# MSP430.net
KiCad netlist of a schematic drawn in Altium Designer
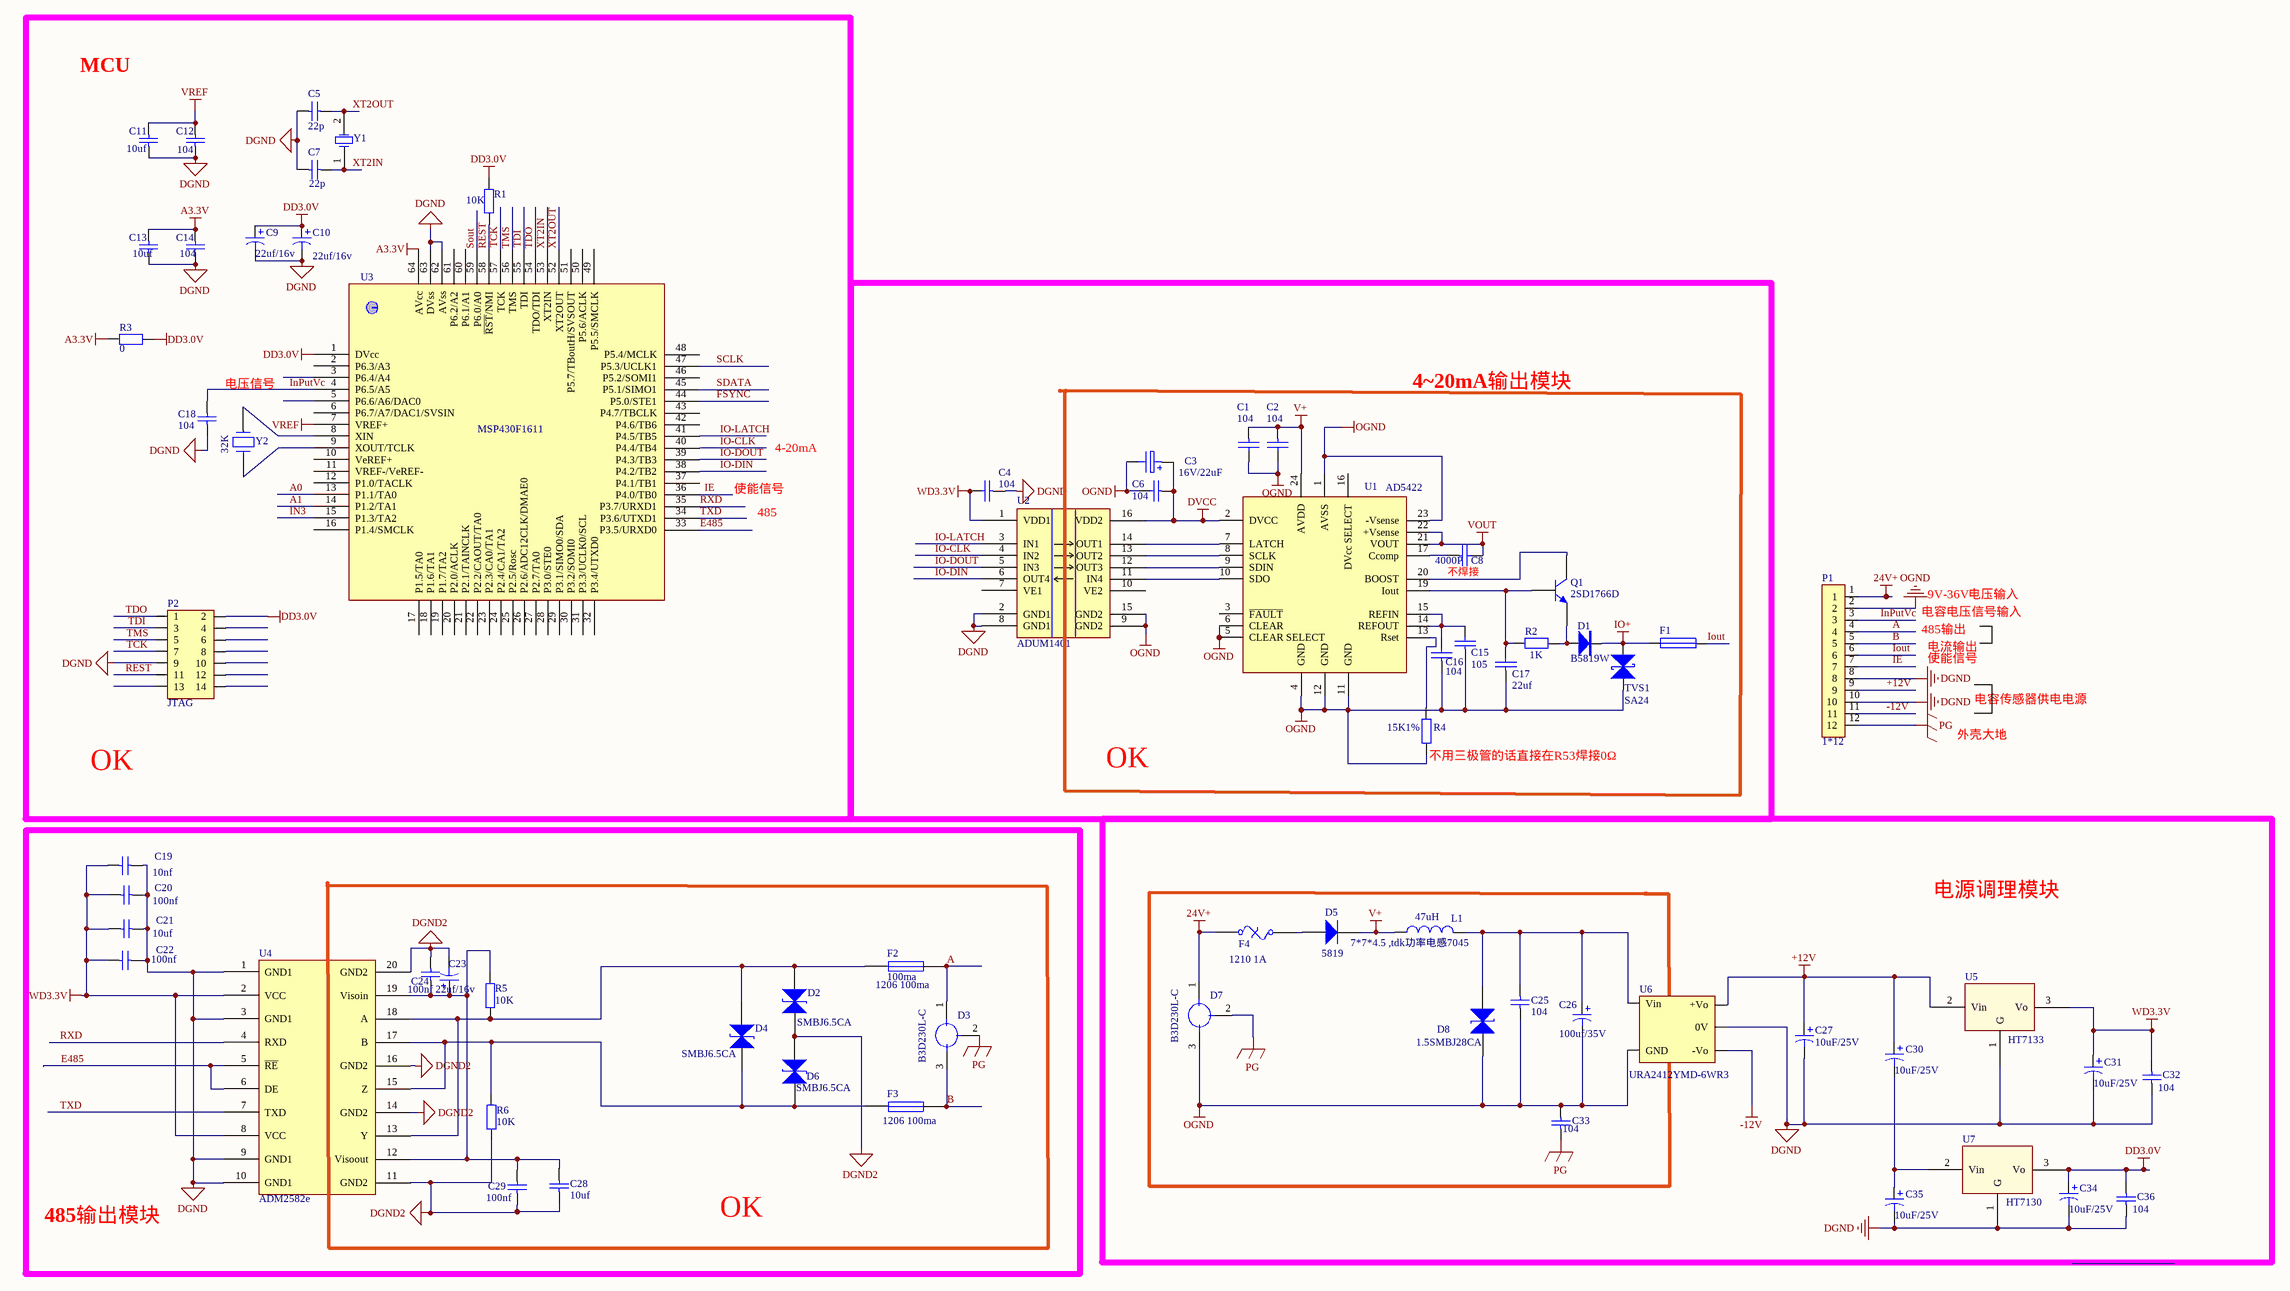
[diagram p0: MSP430.SchDoc]

(export (version "E")
  (design (tool "Eeschema 10.0.6"))
  (components
    (comp (ref "C1") (value "104") (footprint "0805") (libsource (lib "*") (part "CAP")))
    (comp (ref "C2") (value "104") (footprint "0805") (libsource (lib "*") (part "CAP")))
    (comp (ref "C3") (value "16V/22uF") (footprint "3216") (libsource (lib "*") (part "ELECTRO1")))
    (comp (ref "C4") (value "104") (footprint "0805") (libsource (lib "*") (part "CAP")))
    (comp (ref "C5")
      (value "22p")
      (footprint "0805")
      (description "Capacitor")
      (fields (field (name "PUBLISHER") "Altium Limited"))
      (libsource (lib "") (part "Cap_1"))
    )
    (comp (ref "C6") (value "104") (footprint "0805") (libsource (lib "*") (part "CAP")))
    (comp (ref "C7")
      (value "22p")
      (footprint "0805")
      (description "Capacitor")
      (fields (field (name "PUBLISHER") "Altium Limited"))
      (libsource (lib "") (part "Cap_1"))
    )
    (comp (ref "C8") (value "4000P") (footprint "0805") (libsource (lib "*") (part "CAP")))
    (comp (ref "C9")
      (value "22uf/16v")
      (footprint "B型 3528")
      (fields (field (name "ALTIUM_UNNAMED_1") "22uf/16v"))
      (libsource (lib "元器件") (part "Cap Pol2_B"))
    )
    (comp (ref "C10")
      (value "22uf/16v")
      (footprint "B型 3528")
      (fields (field (name "ALTIUM_UNNAMED_1") "22uf/16v"))
      (libsource (lib "元器件") (part "Cap Pol2_B"))
    )
    (comp (ref "C11")
      (value "10uf")
      (footprint "0805")
      (description "Capacitor")
      (fields (field (name "PUBLISHER") "Altium Limited"))
      (libsource (lib "Miscellaneous Devices") (part "Cap"))
    )
    (comp (ref "C12")
      (value "104")
      (footprint "0805")
      (description "Capacitor")
      (fields (field (name "PUBLISHER") "Altium Limited"))
      (libsource (lib "Miscellaneous Devices") (part "Cap"))
    )
    (comp (ref "C13")
      (value "10uf")
      (footprint "0805")
      (description "Capacitor")
      (fields (field (name "PUBLISHER") "Altium Limited"))
      (libsource (lib "Miscellaneous Devices") (part "Cap"))
    )
    (comp (ref "C14")
      (value "104")
      (footprint "0805")
      (description "Capacitor")
      (fields (field (name "PUBLISHER") "Altium Limited"))
      (libsource (lib "Miscellaneous Devices") (part "Cap"))
    )
    (comp (ref "C15") (value "105") (footprint "0805") (libsource (lib "*") (part "CAP")))
    (comp (ref "C16") (value "104") (footprint "0805") (libsource (lib "*") (part "CAP")))
    (comp (ref "C17") (value "22uf") (footprint "0805") (libsource (lib "*") (part "CAP")))
    (comp (ref "C18")
      (value "104")
      (footprint "0805")
      (description "Capacitor")
      (fields (field (name "PUBLISHER") "Altium Limited"))
      (libsource (lib "元器件") (part "Cap_1"))
    )
    (comp (ref "C19")
      (value "10nf")
      (footprint "0805")
      (description "Capacitor")
      (fields (field (name "PUBLISHER") "Altium Limited"))
      (libsource (lib "元器件") (part "Cap_1"))
    )
    (comp (ref "C20")
      (value "100nf")
      (footprint "0805")
      (description "Capacitor")
      (fields (field (name "PUBLISHER") "Altium Limited"))
      (libsource (lib "元器件") (part "Cap_1"))
    )
    (comp (ref "C21")
      (value "10uf")
      (footprint "0805")
      (description "Capacitor")
      (fields (field (name "PUBLISHER") "Altium Limited"))
      (libsource (lib "元器件") (part "Cap_1"))
    )
    (comp (ref "C22")
      (value "100nf")
      (footprint "0805")
      (description "Capacitor")
      (fields (field (name "PUBLISHER") "Altium Limited"))
      (libsource (lib "元器件") (part "Cap_1"))
    )
    (comp (ref "C23")
      (value "22uf/16v")
      (footprint "B型 3528")
      (fields (field (name "ALTIUM_UNNAMED_1") "22uf/16v"))
      (libsource (lib "元器件") (part "Cap Pol2_B"))
    )
    (comp (ref "C24")
      (value "100nf")
      (footprint "0805")
      (description "Capacitor")
      (fields (field (name "PUBLISHER") "Altium Limited"))
      (libsource (lib "元器件") (part "Cap_1"))
    )
    (comp (ref "C25")
      (value "104")
      (footprint "0805")
      (description "Capacitor")
      (fields (field (name "PUBLISHER") "Altium Limited"))
      (libsource (lib "元器件") (part "Cap_1"))
    )
    (comp (ref "C26")
      (value "100uf/35V")
      (footprint "C5X5")
      (description "Polarized Capacitor (Axial)")
      (fields (field (name "Comment") "10uf/35V") (field (name "PUBLISHER") "Altium Limited"))
      (libsource (lib "元器件") (part "Cap Pol2"))
    )
    (comp (ref "C27")
      (value "10uF/25V")
      (footprint "3216")
      (description "Polarized Capacitor (Radial)")
      (fields (field (name "PUBLISHER") "Altium Limited"))
      (libsource (lib "Miscellaneous Devices") (part "Cap Pol1"))
    )
    (comp (ref "C28")
      (value "10uf")
      (footprint "0805")
      (description "Capacitor")
      (fields (field (name "PUBLISHER") "Altium Limited"))
      (libsource (lib "元器件") (part "Cap_1"))
    )
    (comp (ref "C29")
      (value "100nf")
      (footprint "0805")
      (description "Capacitor")
      (fields (field (name "PUBLISHER") "Altium Limited"))
      (libsource (lib "元器件") (part "Cap_1"))
    )
    (comp (ref "C30")
      (value "10uF/25V")
      (footprint "3216")
      (description "Polarized Capacitor (Radial)")
      (fields (field (name "Comment") "10uF") (field (name "PUBLISHER") "Altium Limited"))
      (libsource (lib "Miscellaneous Devices") (part "Cap Pol1"))
    )
    (comp (ref "C31")
      (value "10uF/25V")
      (footprint "3216")
      (description "Polarized Capacitor (Radial)")
      (fields (field (name "Comment") "10uF") (field (name "PUBLISHER") "Altium Limited"))
      (libsource (lib "Miscellaneous Devices") (part "Cap Pol1"))
    )
    (comp (ref "C32")
      (value "104")
      (footprint "0805")
      (description "Capacitor")
      (fields (field (name "PUBLISHER") "Altium Limited"))
      (libsource (lib "") (part "Cap_1"))
    )
    (comp (ref "C33")
      (value "104")
      (footprint "1812")
      (description "Capacitor")
      (fields (field (name "PUBLISHER") "Altium Limited"))
      (libsource (lib "元器件") (part "Cap_1"))
    )
    (comp (ref "C34")
      (value "10uF/25V")
      (footprint "3216")
      (description "Polarized Capacitor (Radial)")
      (fields (field (name "Comment") "10uF") (field (name "PUBLISHER") "Altium Limited"))
      (libsource (lib "Miscellaneous Devices") (part "Cap Pol1"))
    )
    (comp (ref "C35")
      (value "10uF/25V")
      (footprint "3216")
      (description "Polarized Capacitor (Radial)")
      (fields (field (name "Comment") "10uF") (field (name "PUBLISHER") "Altium Limited"))
      (libsource (lib "Miscellaneous Devices") (part "Cap Pol1"))
    )
    (comp (ref "C36")
      (value "104")
      (footprint "0805")
      (description "Capacitor")
      (fields (field (name "PUBLISHER") "Altium Limited"))
      (libsource (lib "") (part "Cap_1"))
    )
    (comp (ref "D1")
      (value "B5819W")
      (footprint "7227-D")
      (description "Diode")
      (libsource (lib "*") (part "B5819W"))
    )
    (comp (ref "D2") (value "SMBJ6.5CA") (footprint "7227-D") (libsource (lib "Tm") (part "TVS")))
    (comp (ref "D3")
      (value "B3D230L-C")
      (footprint "B3D090L-C")
      (libsource (lib "Schlib1") (part "B3D230L-C"))
    )
    (comp (ref "D4") (value "SMBJ6.5CA") (footprint "7227-D") (libsource (lib "Tm") (part "TVS")))
    (comp (ref "D5")
      (value "5819")
      (footprint "7227-D")
      (description "Default Diode")
      (fields (field (name "PUBLISHER") "Altium Limited"))
      (libsource (lib "I5pcb库") (part "Diode"))
    )
    (comp (ref "D6") (value "SMBJ6.5CA") (footprint "7227-D") (libsource (lib "Tm") (part "TVS")))
    (comp (ref "D7")
      (value "B3D230L-C")
      (footprint "B3D090L-C")
      (libsource (lib "Schlib1") (part "B3D230L-C"))
    )
    (comp (ref "D8") (value "1.5SMBJ28CA") (footprint "7227-D") (libsource (lib "Tm") (part "TVS")))
    (comp (ref "F1") (value "~") (footprint "1206") (description "Fuse") (libsource (lib "*") (part "FUSE1")))
    (comp (ref "F2")
      (value "100ma")
      (footprint "1206R")
      (description "Fuse")
      (fields (field (name "PUBLISHER") "Altium Limited"))
      (libsource (lib "Miscellaneous Devices") (part "Fuse 1"))
    )
    (comp (ref "F3")
      (value "100ma")
      (footprint "1206R")
      (description "Fuse")
      (fields (field (name "PUBLISHER") "Altium Limited"))
      (libsource (lib "Miscellaneous Devices") (part "Fuse 1"))
    )
    (comp (ref "F4")
      (value "Fuse Thermal  200ma")
      (footprint "1210")
      (description "Thermal Fuse")
      (fields (field (name "PUBLISHER") "Altium Limited"))
      (libsource (lib "Miscellaneous Devices") (part "Fuse Thermal"))
    )
    (comp (ref "L1")
      (value "47uH")
      (footprint "L7X7")
      (description "Inductor")
      (fields (field (name "Comment") "100uH") (field (name "PUBLISHER") "Altium Limited"))
      (libsource (lib "Miscellaneous Devices") (part "Inductor"))
    )
    (comp (ref "P1") (value "1*12") (libsource (lib "元器件") (part "1*12")))
    (comp (ref "P2") (value "JTAG") (footprint "14缺口") (libsource (lib "元器件") (part "2*7")))
    (comp (ref "Q1")
      (value "2SD1766D")
      (footprint "SOT-89-2")
      (description "NPN General Purpose Amplifier")
      (fields (field (name "PUBLISHER") "Altium Limited"))
      (libsource (lib "元器件") (part "NPN"))
    )
    (comp (ref "R1")
      (value "10K")
      (footprint "0805")
      (description "Resistor")
      (fields (field (name "PUBLISHER") "Altium Limited"))
      (libsource (lib "") (part "Res2_1"))
    )
    (comp (ref "R2")
      (value "1K")
      (footprint "0805")
      (description "Resistor")
      (fields (field (name "PUBLISHER") "Altium Limited"))
      (libsource (lib "") (part "Res2_3"))
    )
    (comp (ref "R3")
      (value "0")
      (footprint "0805")
      (description "Resistor")
      (fields (field (name "PUBLISHER") "Altium Limited"))
      (libsource (lib "Miscellaneous Devices") (part "Res2"))
    )
    (comp (ref "R4")
      (value "15K1%")
      (footprint "0805")
      (description "Resistor")
      (fields (field (name "PUBLISHER") "Altium Limited"))
      (libsource (lib "PRJ_FZ") (part "Res2"))
    )
    (comp (ref "R5")
      (value "10K")
      (footprint "0805")
      (description "Resistor")
      (fields (field (name "PUBLISHER") "Altium Limited"))
      (libsource (lib "") (part "Res2_2"))
    )
    (comp (ref "R6")
      (value "10K")
      (footprint "0805")
      (description "Resistor")
      (fields (field (name "PUBLISHER") "Altium Limited"))
      (libsource (lib "") (part "Res2_2"))
    )
    (comp (ref "TVS1") (value "SA24") (footprint "7227-D") (libsource (lib "*") (part "TVS")))
    (comp (ref "U1") (value "AD5422") (footprint "AD5422") (libsource (lib "元器件") (part "AD5422")))
    (comp (ref "U2") (value "ADUM1401") (footprint "SO16W") (libsource (lib "元器件") (part "ADUM1401")))
    (comp (ref "U3")
      (value "MSP430F1611")
      (footprint "PM")
      (description "MSP430F1611IPM")
      (libsource (lib "*") (part "MSP430F1611IPM"))
    )
    (comp (ref "U4") (value "ADM2582e") (footprint "AM258XXX") (libsource (lib "元器件") (part "ADM258XXX")))
    (comp (ref "U5") (value "HT7133") (footprint "SOT-89-2") (libsource (lib "元器件") (part "HT7150-1")))
    (comp (ref "U6") (value "URA2412YMD-6WR3") (libsource (lib "元器件") (part "URB2409YMD-6WR3_1 双路")))
    (comp (ref "U7") (value "HT7130") (footprint "SOT-89-2") (libsource (lib "元器件") (part "HT7150-1")))
    (comp (ref "Y1")
      (value "8M")
      (footprint "5032")
      (description "Crystal Oscillator")
      (fields (field (name "PUBLISHER") "Altium Limited"))
      (libsource (lib "Miscellaneous Devices") (part "XTAL"))
    )
    (comp (ref "Y2")
      (value "32K")
      (footprint "FC-135")
      (description "Crystal")
      (libsource (lib "*") (part "CRYSTAL"))
    )
  )
  (nets
    (net (code "1") (name "+12V") (class "Default")
      (node (ref "C27") (pin "1") (pinfunction "1_1") (pintype "passive"))
      (node (ref "C30") (pin "1") (pinfunction "1_1") (pintype "passive"))
      (node (ref "P1") (pin "9") (pinfunction "9_9") (pintype "passive"))
      (node (ref "U5") (pin "2") (pinfunction "Vin_2") (pintype "passive"))
    )
    (net (code "2") (name "-12V") (class "Default")
      (node (ref "P1") (pin "11") (pinfunction "11_11") (pintype "passive"))
      (node (ref "U6") (pin "4") (pinfunction "-Vo_4") (pintype "passive"))
    )
    (net (code "3") (name "/A") (class "Default")
      (node (ref "D3") (pin "1") (pinfunction "1_1") (pintype "passive"))
      (node (ref "F2") (pin "2") (pinfunction "2_2") (pintype "passive"))
      (node (ref "P1") (pin "4") (pinfunction "4_4") (pintype "passive"))
    )
    (net (code "4") (name "/A0") (class "Default")
      (node (ref "U3") (pin "13") (pinfunction "P1.1/TA0_13") (pintype "passive"))
    )
    (net (code "5") (name "/A1") (class "Default")
      (node (ref "U3") (pin "14") (pinfunction "P1.2/TA1_14") (pintype "passive"))
    )
    (net (code "6") (name "/B") (class "Default")
      (node (ref "D3") (pin "3") (pinfunction "3_3") (pintype "passive"))
      (node (ref "F3") (pin "2") (pinfunction "2_2") (pintype "passive"))
      (node (ref "P1") (pin "5") (pinfunction "5_5") (pintype "passive"))
    )
    (net (code "7") (name "/E485") (class "Default")
      (node (ref "U3") (pin "33") (pinfunction "P3.5/URXD0_33") (pintype "passive"))
      (node (ref "U4") (pin "5") (pinfunction "~{RE}_5") (pintype "passive"))
      (node (ref "U4") (pin "6") (pinfunction "DE_6") (pintype "passive"))
    )
    (net (code "8") (name "/FSYNC") (class "Default")
      (node (ref "U3") (pin "44") (pinfunction "P5.0/STE1_44") (pintype "passive"))
    )
    (net (code "9") (name "/IE") (class "Default")
      (node (ref "P1") (pin "7") (pinfunction "7_7") (pintype "passive"))
      (node (ref "U3") (pin "36") (pinfunction "P4.0/TB0_36") (pintype "passive"))
    )
    (net (code "10") (name "/IN3") (class "Default")
      (node (ref "U3") (pin "15") (pinfunction "P1.3/TA2_15") (pintype "passive"))
    )
    (net (code "11") (name "/IO-CLK") (class "Default")
      (node (ref "U2") (pin "4") (pinfunction "IN2_4") (pintype "passive"))
      (node (ref "U3") (pin "40") (pinfunction "P4.4/TB4_40") (pintype "passive"))
    )
    (net (code "12") (name "/IO-DIN") (class "Default")
      (node (ref "U2") (pin "6") (pinfunction "OUT4_6") (pintype "passive"))
      (node (ref "U3") (pin "38") (pinfunction "P4.2/TB2_38") (pintype "passive"))
    )
    (net (code "13") (name "/IO-DOUT") (class "Default")
      (node (ref "U2") (pin "5") (pinfunction "IN3_5") (pintype "passive"))
      (node (ref "U3") (pin "39") (pinfunction "P4.3/TB3_39") (pintype "passive"))
    )
    (net (code "14") (name "/IO-LATCH") (class "Default")
      (node (ref "U2") (pin "3") (pinfunction "IN1_3") (pintype "passive"))
      (node (ref "U3") (pin "41") (pinfunction "P4.5/TB5_41") (pintype "passive"))
    )
    (net (code "15") (name "/InPutVc") (class "Default")
      (node (ref "C18") (pin "2") (pinfunction "2_2") (pintype "passive"))
      (node (ref "P1") (pin "3") (pinfunction "3_3") (pintype "passive"))
      (node (ref "U3") (pin "4") (pinfunction "P6.5/A5_4") (pintype "passive"))
    )
    (net (code "16") (name "/Iout") (class "Default")
      (node (ref "F1") (pin "1") (pinfunction "1_1") (pintype "passive"))
      (node (ref "P1") (pin "6") (pinfunction "6_6") (pintype "passive"))
    )
    (net (code "17") (name "/REST") (class "Default")
      (node (ref "P2") (pin "11") (pinfunction "11_11") (pintype "passive"))
      (node (ref "R1") (pin "1") (pinfunction "1_1") (pintype "passive"))
      (node (ref "U3") (pin "58") (pinfunction "~{RST}/NMI_58") (pintype "passive"))
    )
    (net (code "18") (name "/RXD") (class "Default")
      (node (ref "U3") (pin "35") (pinfunction "P3.7/URXD1_35") (pintype "passive"))
      (node (ref "U4") (pin "4") (pinfunction "RXD_4") (pintype "passive"))
    )
    (net (code "19") (name "/SCLK") (class "Default")
      (node (ref "U3") (pin "47") (pinfunction "P5.3/UCLK1_47") (pintype "passive"))
    )
    (net (code "20") (name "/SDATA") (class "Default")
      (node (ref "U3") (pin "45") (pinfunction "P5.1/SIMO1_45") (pintype "passive"))
    )
    (net (code "21") (name "/Sout") (class "Default")
      (node (ref "U3") (pin "59") (pinfunction "P6.0/A0_59") (pintype "passive"))
    )
    (net (code "22") (name "/TCK") (class "Default")
      (node (ref "P2") (pin "7") (pinfunction "7_7") (pintype "passive"))
      (node (ref "U3") (pin "57") (pinfunction "TCK_57") (pintype "passive"))
    )
    (net (code "23") (name "/TDI") (class "Default")
      (node (ref "P2") (pin "3") (pinfunction "3_3") (pintype "passive"))
      (node (ref "U3") (pin "55") (pinfunction "TDI_55") (pintype "passive"))
    )
    (net (code "24") (name "/TDO") (class "Default")
      (node (ref "P2") (pin "1") (pinfunction "1_1") (pintype "passive"))
      (node (ref "U3") (pin "54") (pinfunction "TDO/TDI_54") (pintype "passive"))
    )
    (net (code "25") (name "/TMS") (class "Default")
      (node (ref "P2") (pin "5") (pinfunction "5_5") (pintype "passive"))
      (node (ref "U3") (pin "56") (pinfunction "TMS_56") (pintype "passive"))
    )
    (net (code "26") (name "/TXD") (class "Default")
      (node (ref "U3") (pin "34") (pinfunction "P3.6/UTXD1_34") (pintype "passive"))
      (node (ref "U4") (pin "7") (pinfunction "TXD_7") (pintype "passive"))
    )
    (net (code "27") (name "/XT2IN") (class "Default")
      (node (ref "C7") (pin "1") (pinfunction "1_1") (pintype "passive"))
      (node (ref "U3") (pin "53") (pinfunction "XT2IN_53") (pintype "passive"))
      (node (ref "Y1") (pin "1") (pinfunction "OSC1_1") (pintype "passive"))
    )
    (net (code "28") (name "/XT2OUT") (class "Default")
      (node (ref "C5") (pin "1") (pinfunction "1_1") (pintype "passive"))
      (node (ref "U3") (pin "52") (pinfunction "XT2OUT_52") (pintype "passive"))
      (node (ref "Y1") (pin "2") (pinfunction "OSC2_2") (pintype "passive"))
    )
    (net (code "29") (name "24V+") (class "Default")
      (node (ref "D7") (pin "1") (pinfunction "1_1") (pintype "passive"))
      (node (ref "F4") (pin "1") (pinfunction "1_1") (pintype "passive"))
      (node (ref "P1") (pin "1") (pinfunction "1_1") (pintype "passive"))
    )
    (net (code "30") (name "A3.3V") (class "Default")
      (node (ref "C13") (pin "1") (pinfunction "1_1") (pintype "passive"))
      (node (ref "C14") (pin "1") (pinfunction "1_1") (pintype "passive"))
      (node (ref "R3") (pin "1") (pinfunction "1_1") (pintype "passive"))
      (node (ref "U3") (pin "64") (pinfunction "AVcc_64") (pintype "passive"))
    )
    (net (code "31") (name "DD3.0V") (class "Default")
      (node (ref "C10") (pin "1") (pinfunction "1_1") (pintype "passive"))
      (node (ref "C34") (pin "1") (pinfunction "1_1") (pintype "passive"))
      (node (ref "C36") (pin "2") (pinfunction "2_2") (pintype "passive"))
      (node (ref "C9") (pin "1") (pinfunction "1_1") (pintype "passive"))
      (node (ref "P2") (pin "2") (pinfunction "2_2") (pintype "passive"))
      (node (ref "R1") (pin "2") (pinfunction "2_2") (pintype "passive"))
      (node (ref "R3") (pin "2") (pinfunction "2_2") (pintype "passive"))
      (node (ref "U3") (pin "1") (pinfunction "DVcc_1") (pintype "passive"))
      (node (ref "U7") (pin "3") (pinfunction "Vo_3") (pintype "passive"))
    )
    (net (code "32") (name "DGND") (class "Default")
      (node (ref "C10") (pin "2") (pinfunction "2_2") (pintype "passive"))
      (node (ref "C11") (pin "2") (pinfunction "2_2") (pintype "passive"))
      (node (ref "C12") (pin "2") (pinfunction "2_2") (pintype "passive"))
      (node (ref "C13") (pin "2") (pinfunction "2_2") (pintype "passive"))
      (node (ref "C14") (pin "2") (pinfunction "2_2") (pintype "passive"))
      (node (ref "C18") (pin "1") (pinfunction "1_1") (pintype "passive"))
      (node (ref "C19") (pin "1") (pinfunction "1_1") (pintype "passive"))
      (node (ref "C20") (pin "1") (pinfunction "1_1") (pintype "passive"))
      (node (ref "C21") (pin "1") (pinfunction "1_1") (pintype "passive"))
      (node (ref "C22") (pin "1") (pinfunction "1_1") (pintype "passive"))
      (node (ref "C27") (pin "2") (pinfunction "2_2") (pintype "passive"))
      (node (ref "C31") (pin "2") (pinfunction "2_2") (pintype "passive"))
      (node (ref "C32") (pin "1") (pinfunction "1_1") (pintype "passive"))
      (node (ref "C34") (pin "2") (pinfunction "2_2") (pintype "passive"))
      (node (ref "C35") (pin "2") (pinfunction "2_2") (pintype "passive"))
      (node (ref "C36") (pin "1") (pinfunction "1_1") (pintype "passive"))
      (node (ref "C4") (pin "1") (pintype "passive"))
      (node (ref "C5") (pin "2") (pinfunction "2_2") (pintype "passive"))
      (node (ref "C7") (pin "2") (pinfunction "2_2") (pintype "passive"))
      (node (ref "C9") (pin "2") (pinfunction "2_2") (pintype "passive"))
      (node (ref "P1") (pin "10") (pinfunction "10_10") (pintype "passive"))
      (node (ref "P1") (pin "8") (pinfunction "8_8") (pintype "passive"))
      (node (ref "P2") (pin "9") (pinfunction "9_9") (pintype "passive"))
      (node (ref "U2") (pin "2") (pinfunction "GND1_2") (pintype "passive"))
      (node (ref "U2") (pin "8") (pinfunction "GND1_8") (pintype "passive"))
      (node (ref "U3") (pin "62") (pinfunction "AVss_62") (pintype "passive"))
      (node (ref "U3") (pin "63") (pinfunction "DVss_63") (pintype "passive"))
      (node (ref "U4") (pin "1") (pinfunction "GND1_1") (pintype "passive"))
      (node (ref "U4") (pin "10") (pinfunction "GND1_10") (pintype "passive"))
      (node (ref "U4") (pin "3") (pinfunction "GND1_3") (pintype "passive"))
      (node (ref "U4") (pin "9") (pinfunction "GND1_9") (pintype "passive"))
      (node (ref "U5") (pin "1") (pinfunction "G_1") (pintype "passive"))
      (node (ref "U6") (pin "4") (pinfunction "0V_4") (pintype "passive"))
      (node (ref "U7") (pin "1") (pinfunction "G_1") (pintype "passive"))
    )
    (net (code "33") (name "DGND2") (class "Default")
      (node (ref "C23") (pin "2") (pinfunction "2_2") (pintype "passive"))
      (node (ref "C24") (pin "1") (pinfunction "1_1") (pintype "passive"))
      (node (ref "C28") (pin "2") (pinfunction "2_2") (pintype "passive"))
      (node (ref "C29") (pin "2") (pinfunction "2_2") (pintype "passive"))
      (node (ref "D2") (pin "1") (pinfunction "K_1") (pintype "passive"))
      (node (ref "D6") (pin "1") (pinfunction "K_1") (pintype "passive"))
      (node (ref "R6") (pin "2") (pinfunction "2_2") (pintype "passive"))
      (node (ref "U4") (pin "11") (pinfunction "GND2_11") (pintype "passive"))
      (node (ref "U4") (pin "14") (pinfunction "GND2_14") (pintype "passive"))
      (node (ref "U4") (pin "16") (pinfunction "GND2_16") (pintype "passive"))
      (node (ref "U4") (pin "20") (pinfunction "GND2_20") (pintype "passive"))
    )
    (net (code "34") (name "DVCC") (class "Default")
      (node (ref "C3") (pin "1") (pintype "passive"))
      (node (ref "C6") (pin "1") (pintype "passive"))
      (node (ref "U1") (pin "2") (pinfunction "DVCC_2") (pintype "passive"))
      (node (ref "U2") (pin "16") (pinfunction "VDD2_16") (pintype "passive"))
    )
    (net (code "35") (name "IO+") (class "Default")
      (node (ref "D1") (pin "2") (pinfunction "K_2") (pintype "passive"))
      (node (ref "F1") (pin "2") (pinfunction "2_2") (pintype "passive"))
      (node (ref "TVS1") (pin "2") (pinfunction "K_2") (pintype "passive"))
    )
    (net (code "36") (name "Net-(D1-A)") (class "Default")
      (node (ref "D1") (pin "1") (pinfunction "A_1") (pintype "passive"))
      (node (ref "Q1") (pin "3") (pinfunction "E_3") (pintype "passive"))
      (node (ref "R2") (pin "1") (pinfunction "1_1") (pintype "passive"))
    )
    (net (code "37") (name "Net-(D2-A)") (class "Default")
      (node (ref "D2") (pin "2") (pinfunction "A_2") (pintype "passive"))
      (node (ref "D4") (pin "2") (pinfunction "A_2") (pintype "passive"))
      (node (ref "F2") (pin "1") (pinfunction "1_1") (pintype "passive"))
      (node (ref "R5") (pin "2") (pinfunction "2_2") (pintype "passive"))
      (node (ref "U4") (pin "13") (pinfunction "Y_13") (pintype "passive"))
      (node (ref "U4") (pin "18") (pinfunction "A_18") (pintype "passive"))
    )
    (net (code "38") (name "Net-(D4-K)") (class "Default")
      (node (ref "D4") (pin "1") (pinfunction "K_1") (pintype "passive"))
      (node (ref "D6") (pin "2") (pinfunction "A_2") (pintype "passive"))
      (node (ref "F3") (pin "1") (pinfunction "1_1") (pintype "passive"))
      (node (ref "R6") (pin "1") (pinfunction "1_1") (pintype "passive"))
      (node (ref "U4") (pin "15") (pinfunction "Z_15") (pintype "passive"))
      (node (ref "U4") (pin "17") (pinfunction "B_17") (pintype "passive"))
    )
    (net (code "39") (name "Net-(D5-A)") (class "Default")
      (node (ref "D5") (pin "1") (pinfunction "A_1") (pintype "passive"))
      (node (ref "F4") (pin "2") (pinfunction "2_2") (pintype "passive"))
    )
    (net (code "40") (name "Net-(D8-A)") (class "Default")
      (node (ref "C25") (pin "2") (pinfunction "2_2") (pintype "passive"))
      (node (ref "C26") (pin "1") (pinfunction "1_1") (pintype "passive"))
      (node (ref "D8") (pin "2") (pinfunction "A_2") (pintype "passive"))
      (node (ref "L1") (pin "2") (pinfunction "2_2") (pintype "passive"))
      (node (ref "U6") (pin "2") (pinfunction "Vin_2") (pintype "passive"))
    )
    (net (code "41") (name "Net-(Q1-B)") (class "Default")
      (node (ref "C17") (pin "2") (pintype "passive"))
      (node (ref "Q1") (pin "1") (pinfunction "B_1") (pintype "passive"))
      (node (ref "R2") (pin "2") (pinfunction "2_2") (pintype "passive"))
      (node (ref "U1") (pin "19") (pinfunction "Iout_19") (pintype "passive"))
    )
    (net (code "42") (name "Net-(Q1-C)") (class "Default")
      (node (ref "Q1") (pin "2") (pinfunction "C_2") (pintype "passive"))
      (node (ref "U1") (pin "20") (pinfunction "BOOST_20") (pintype "passive"))
    )
    (net (code "43") (name "Net-(U1-Ccomp)") (class "Default")
      (node (ref "C8") (pin "1") (pintype "passive"))
      (node (ref "U1") (pin "17") (pinfunction "Ccomp_17") (pintype "passive"))
    )
    (net (code "44") (name "Net-(U1-LATCH)") (class "Default")
      (node (ref "U1") (pin "7") (pinfunction "LATCH_7") (pintype "passive"))
      (node (ref "U2") (pin "14") (pinfunction "OUT1_14") (pintype "passive"))
    )
    (net (code "45") (name "Net-(U1-REFIN)") (class "Default")
      (node (ref "C15") (pin "2") (pintype "passive"))
      (node (ref "C16") (pin "2") (pintype "passive"))
      (node (ref "U1") (pin "14") (pinfunction "REFOUT_14") (pintype "passive"))
      (node (ref "U1") (pin "15") (pinfunction "REFIN_15") (pintype "passive"))
    )
    (net (code "46") (name "Net-(U1-Rset)") (class "Default")
      (node (ref "R4") (pin "1") (pinfunction "1_1") (pintype "passive"))
      (node (ref "U1") (pin "13") (pinfunction "Rset_13") (pintype "passive"))
    )
    (net (code "47") (name "Net-(U1-SCLK)") (class "Default")
      (node (ref "U1") (pin "8") (pinfunction "SCLK_8") (pintype "passive"))
      (node (ref "U2") (pin "13") (pinfunction "OUT2_13") (pintype "passive"))
    )
    (net (code "48") (name "Net-(U1-SDIN)") (class "Default")
      (node (ref "U1") (pin "9") (pinfunction "SDIN_9") (pintype "passive"))
      (node (ref "U2") (pin "12") (pinfunction "OUT3_12") (pintype "passive"))
    )
    (net (code "49") (name "Net-(U1-SDO)") (class "Default")
      (node (ref "U1") (pin "10") (pinfunction "SDO_10") (pintype "passive"))
      (node (ref "U2") (pin "11") (pinfunction "IN4_11") (pintype "passive"))
    )
    (net (code "50") (name "Net-(U3-XIN)") (class "Default")
      (node (ref "U3") (pin "8") (pinfunction "XIN_8") (pintype "passive"))
      (node (ref "Y2") (pin "1") (pinfunction "1_1") (pintype "passive"))
    )
    (net (code "51") (name "Net-(U3-XOUT{slash}TCLK)") (class "Default")
      (node (ref "U3") (pin "9") (pinfunction "XOUT/TCLK_9") (pintype "passive"))
      (node (ref "Y2") (pin "2") (pinfunction "2_2") (pintype "passive"))
    )
    (net (code "52") (name "Net-(U4-Visoin)") (class "Default")
      (node (ref "C23") (pin "1") (pinfunction "1_1") (pintype "passive"))
      (node (ref "C24") (pin "2") (pinfunction "2_2") (pintype "passive"))
      (node (ref "C28") (pin "1") (pinfunction "1_1") (pintype "passive"))
      (node (ref "C29") (pin "1") (pinfunction "1_1") (pintype "passive"))
      (node (ref "R5") (pin "1") (pinfunction "1_1") (pintype "passive"))
      (node (ref "U4") (pin "12") (pinfunction "Visoout_12") (pintype "passive"))
      (node (ref "U4") (pin "19") (pinfunction "Visoin_19") (pintype "passive"))
    )
    (net (code "53") (name "Net-(U7-Vin)") (class "Default")
      (node (ref "C30") (pin "2") (pinfunction "2_2") (pintype "passive"))
      (node (ref "C35") (pin "1") (pinfunction "1_1") (pintype "passive"))
      (node (ref "U7") (pin "2") (pinfunction "Vin_2") (pintype "passive"))
    )
    (net (code "54") (name "OGND") (class "Default")
      (node (ref "C1") (pin "2") (pintype "passive"))
      (node (ref "C15") (pin "1") (pintype "passive"))
      (node (ref "C16") (pin "1") (pintype "passive"))
      (node (ref "C17") (pin "1") (pintype "passive"))
      (node (ref "C2") (pin "2") (pintype "passive"))
      (node (ref "C25") (pin "1") (pinfunction "1_1") (pintype "passive"))
      (node (ref "C26") (pin "2") (pinfunction "2_2") (pintype "passive"))
      (node (ref "C3") (pin "2") (pintype "passive"))
      (node (ref "C33") (pin "2") (pinfunction "2_2") (pintype "passive"))
      (node (ref "C6") (pin "2") (pintype "passive"))
      (node (ref "D7") (pin "3") (pinfunction "3_3") (pintype "passive"))
      (node (ref "D8") (pin "1") (pinfunction "K_1") (pintype "passive"))
      (node (ref "P1") (pin "2") (pinfunction "2_2") (pintype "passive"))
      (node (ref "R4") (pin "2") (pinfunction "2_2") (pintype "passive"))
      (node (ref "TVS1") (pin "1") (pinfunction "A_1") (pintype "passive"))
      (node (ref "U1") (pin "1") (pinfunction "AVSS_1") (pintype "passive"))
      (node (ref "U1") (pin "11") (pinfunction "GND_11") (pintype "passive"))
      (node (ref "U1") (pin "12") (pinfunction "GND_12") (pintype "passive"))
      (node (ref "U1") (pin "23") (pinfunction "-Vsense_23") (pintype "passive"))
      (node (ref "U1") (pin "4") (pinfunction "GND_4") (pintype "passive"))
      (node (ref "U1") (pin "5") (pinfunction "CLEAR_SELECT_5") (pintype "passive"))
      (node (ref "U1") (pin "6") (pinfunction "CLEAR_6") (pintype "passive"))
      (node (ref "U2") (pin "15") (pinfunction "GND2_15") (pintype "passive"))
      (node (ref "U2") (pin "9") (pinfunction "GND2_9") (pintype "passive"))
      (node (ref "U6") (pin "1") (pinfunction "GND_1") (pintype "passive"))
    )
    (net (code "55") (name "PG") (class "Default")
      (node (ref "C33") (pin "1") (pinfunction "1_1") (pintype "passive"))
      (node (ref "D3") (pin "2") (pinfunction "2_2") (pintype "passive"))
      (node (ref "D7") (pin "2") (pinfunction "2_2") (pintype "passive"))
      (node (ref "P1") (pin "12") (pinfunction "12_12") (pintype "passive"))
    )
    (net (code "56") (name "V+") (class "Default")
      (node (ref "C1") (pin "1") (pintype "passive"))
      (node (ref "C2") (pin "1") (pintype "passive"))
      (node (ref "D5") (pin "2") (pinfunction "K_2") (pintype "passive"))
      (node (ref "L1") (pin "1") (pinfunction "1_1") (pintype "passive"))
      (node (ref "U1") (pin "24") (pinfunction "AVDD_24") (pintype "passive"))
    )
    (net (code "57") (name "VOUT") (class "Default")
      (node (ref "C8") (pin "2") (pintype "passive"))
      (node (ref "U1") (pin "21") (pinfunction "VOUT_21") (pintype "passive"))
      (node (ref "U1") (pin "22") (pinfunction "+Vsense_22") (pintype "passive"))
    )
    (net (code "58") (name "VREF") (class "Default")
      (node (ref "C11") (pin "1") (pinfunction "1_1") (pintype "passive"))
      (node (ref "C12") (pin "1") (pinfunction "1_1") (pintype "passive"))
      (node (ref "U3") (pin "7") (pinfunction "VREF+_7") (pintype "passive"))
    )
    (net (code "59") (name "WD3.3V") (class "Default")
      (node (ref "C19") (pin "2") (pinfunction "2_2") (pintype "passive"))
      (node (ref "C20") (pin "2") (pinfunction "2_2") (pintype "passive"))
      (node (ref "C21") (pin "2") (pinfunction "2_2") (pintype "passive"))
      (node (ref "C22") (pin "2") (pinfunction "2_2") (pintype "passive"))
      (node (ref "C31") (pin "1") (pinfunction "1_1") (pintype "passive"))
      (node (ref "C32") (pin "2") (pinfunction "2_2") (pintype "passive"))
      (node (ref "C4") (pin "2") (pintype "passive"))
      (node (ref "U2") (pin "1") (pinfunction "VDD1_1") (pintype "passive"))
      (node (ref "U4") (pin "2") (pinfunction "VCC_2") (pintype "passive"))
      (node (ref "U4") (pin "8") (pinfunction "VCC_8") (pintype "passive"))
      (node (ref "U5") (pin "3") (pinfunction "Vo_3") (pintype "passive"))
    )
    (net (code "60") (name "unconnected-(P2-Pad4)") (class "Default")
      (node (ref "P2") (pin "4") (pinfunction "4_4") (pintype "passive"))
    )
    (net (code "61") (name "unconnected-(P2-Pad6)") (class "Default")
      (node (ref "P2") (pin "6") (pinfunction "6_6") (pintype "passive"))
    )
    (net (code "62") (name "unconnected-(P2-Pad8)") (class "Default")
      (node (ref "P2") (pin "8") (pinfunction "8_8") (pintype "passive"))
    )
    (net (code "63") (name "unconnected-(P2-Pad10)") (class "Default")
      (node (ref "P2") (pin "10") (pinfunction "10_10") (pintype "passive"))
    )
    (net (code "64") (name "unconnected-(P2-Pad12)") (class "Default")
      (node (ref "P2") (pin "12") (pinfunction "12_12") (pintype "passive"))
    )
    (net (code "65") (name "unconnected-(P2-Pad13)") (class "Default")
      (node (ref "P2") (pin "13") (pinfunction "13_13") (pintype "passive"))
    )
    (net (code "66") (name "unconnected-(P2-Pad14)") (class "Default")
      (node (ref "P2") (pin "14") (pinfunction "14_14") (pintype "passive"))
    )
    (net (code "67") (name "unconnected-(U1-DVcc_SELECT-Pad16)") (class "Default")
      (node (ref "U1") (pin "16") (pinfunction "DVcc_SELECT_16") (pintype "passive"))
    )
    (net (code "68") (name "unconnected-(U1-~{FAULT}-Pad3)") (class "Default")
      (node (ref "U1") (pin "3") (pinfunction "~{FAULT}_3") (pintype "passive"))
    )
    (net (code "69") (name "unconnected-(U2-VE1-Pad7)") (class "Default")
      (node (ref "U2") (pin "7") (pinfunction "VE1_7") (pintype "passive"))
    )
    (net (code "70") (name "unconnected-(U2-VE2-Pad10)") (class "Default")
      (node (ref "U2") (pin "10") (pinfunction "VE2_10") (pintype "passive"))
    )
    (net (code "71") (name "unconnected-(U3-P1.0{slash}TACLK-Pad12)") (class "Default")
      (node (ref "U3") (pin "12") (pinfunction "P1.0/TACLK_12") (pintype "passive"))
    )
    (net (code "72") (name "unconnected-(U3-P1.4{slash}SMCLK-Pad16)") (class "Default")
      (node (ref "U3") (pin "16") (pinfunction "P1.4/SMCLK_16") (pintype "passive"))
    )
    (net (code "73") (name "unconnected-(U3-P1.5{slash}TA0-Pad17)") (class "Default")
      (node (ref "U3") (pin "17") (pinfunction "P1.5/TA0_17") (pintype "passive"))
    )
    (net (code "74") (name "unconnected-(U3-P1.6{slash}TA1-Pad18)") (class "Default")
      (node (ref "U3") (pin "18") (pinfunction "P1.6/TA1_18") (pintype "passive"))
    )
    (net (code "75") (name "unconnected-(U3-P1.7{slash}TA2-Pad19)") (class "Default")
      (node (ref "U3") (pin "19") (pinfunction "P1.7/TA2_19") (pintype "passive"))
    )
    (net (code "76") (name "unconnected-(U3-P2.0{slash}ACLK-Pad20)") (class "Default")
      (node (ref "U3") (pin "20") (pinfunction "P2.0/ACLK_20") (pintype "passive"))
    )
    (net (code "77") (name "unconnected-(U3-P2.1{slash}TAINCLK-Pad21)") (class "Default")
      (node (ref "U3") (pin "21") (pinfunction "P2.1/TAINCLK_21") (pintype "passive"))
    )
    (net (code "78") (name "unconnected-(U3-P2.2{slash}CAOUT{slash}TA0-Pad22)") (class "Default")
      (node (ref "U3") (pin "22") (pinfunction "P2.2/CAOUT/TA0_22") (pintype "passive"))
    )
    (net (code "79") (name "unconnected-(U3-P2.3{slash}CA0{slash}TA1-Pad23)") (class "Default")
      (node (ref "U3") (pin "23") (pinfunction "P2.3/CA0/TA1_23") (pintype "passive"))
    )
    (net (code "80") (name "unconnected-(U3-P2.4{slash}CA1{slash}TA2-Pad24)") (class "Default")
      (node (ref "U3") (pin "24") (pinfunction "P2.4/CA1/TA2_24") (pintype "passive"))
    )
    (net (code "81") (name "unconnected-(U3-P2.5{slash}Rosc-Pad25)") (class "Default")
      (node (ref "U3") (pin "25") (pinfunction "P2.5/Rosc_25") (pintype "passive"))
    )
    (net (code "82") (name "unconnected-(U3-P2.6{slash}ADC12CLK{slash}DMAE0-Pad26)") (class "Default")
      (node (ref "U3") (pin "26") (pinfunction "P2.6/ADC12CLK/DMAE0_26") (pintype "passive"))
    )
    (net (code "83") (name "unconnected-(U3-P2.7{slash}TA0-Pad27)") (class "Default")
      (node (ref "U3") (pin "27") (pinfunction "P2.7/TA0_27") (pintype "passive"))
    )
    (net (code "84") (name "unconnected-(U3-P3.0{slash}STE0-Pad28)") (class "Default")
      (node (ref "U3") (pin "28") (pinfunction "P3.0/STE0_28") (pintype "passive"))
    )
    (net (code "85") (name "unconnected-(U3-P3.1{slash}SIMO0{slash}SDA-Pad29)") (class "Default")
      (node (ref "U3") (pin "29") (pinfunction "P3.1/SIMO0/SDA_29") (pintype "passive"))
    )
    (net (code "86") (name "unconnected-(U3-P3.2{slash}SOMI0-Pad30)") (class "Default")
      (node (ref "U3") (pin "30") (pinfunction "P3.2/SOMI0_30") (pintype "passive"))
    )
    (net (code "87") (name "unconnected-(U3-P3.3{slash}UCLK0{slash}SCL-Pad31)") (class "Default")
      (node (ref "U3") (pin "31") (pinfunction "P3.3/UCLK0/SCL_31") (pintype "passive"))
    )
    (net (code "88") (name "unconnected-(U3-P3.4{slash}UTXD0-Pad32)") (class "Default")
      (node (ref "U3") (pin "32") (pinfunction "P3.4/UTXD0_32") (pintype "passive"))
    )
    (net (code "89") (name "unconnected-(U3-P4.1{slash}TB1-Pad37)") (class "Default")
      (node (ref "U3") (pin "37") (pinfunction "P4.1/TB1_37") (pintype "passive"))
    )
    (net (code "90") (name "unconnected-(U3-P4.6{slash}TB6-Pad42)") (class "Default")
      (node (ref "U3") (pin "42") (pinfunction "P4.6/TB6_42") (pintype "passive"))
    )
    (net (code "91") (name "unconnected-(U3-P4.7{slash}TBCLK-Pad43)") (class "Default")
      (node (ref "U3") (pin "43") (pinfunction "P4.7/TBCLK_43") (pintype "passive"))
    )
    (net (code "92") (name "unconnected-(U3-P5.2{slash}SOMI1-Pad46)") (class "Default")
      (node (ref "U3") (pin "46") (pinfunction "P5.2/SOMI1_46") (pintype "passive"))
    )
    (net (code "93") (name "unconnected-(U3-P5.4{slash}MCLK-Pad48)") (class "Default")
      (node (ref "U3") (pin "48") (pinfunction "P5.4/MCLK_48") (pintype "passive"))
    )
    (net (code "94") (name "unconnected-(U3-P5.5{slash}SMCLK-Pad49)") (class "Default")
      (node (ref "U3") (pin "49") (pinfunction "P5.5/SMCLK_49") (pintype "passive"))
    )
    (net (code "95") (name "unconnected-(U3-P5.6{slash}ACLK-Pad50)") (class "Default")
      (node (ref "U3") (pin "50") (pinfunction "P5.6/ACLK_50") (pintype "passive"))
    )
    (net (code "96") (name "unconnected-(U3-P5.7{slash}TBoutH{slash}SVSOUT-Pad51)") (class "Default")
      (node (ref "U3") (pin "51") (pinfunction "P5.7/TBoutH/SVSOUT_51") (pintype "passive"))
    )
    (net (code "97") (name "unconnected-(U3-P6.1{slash}A1-Pad60)") (class "Default")
      (node (ref "U3") (pin "60") (pinfunction "P6.1/A1_60") (pintype "passive"))
    )
    (net (code "98") (name "unconnected-(U3-P6.2{slash}A2-Pad61)") (class "Default")
      (node (ref "U3") (pin "61") (pinfunction "P6.2/A2_61") (pintype "passive"))
    )
    (net (code "99") (name "unconnected-(U3-P6.3{slash}A3-Pad2)") (class "Default")
      (node (ref "U3") (pin "2") (pinfunction "P6.3/A3_2") (pintype "passive"))
    )
    (net (code "100") (name "unconnected-(U3-P6.4{slash}A4-Pad3)") (class "Default")
      (node (ref "U3") (pin "3") (pinfunction "P6.4/A4_3") (pintype "passive"))
    )
    (net (code "101") (name "unconnected-(U3-P6.6{slash}A6{slash}DAC0-Pad5)") (class "Default")
      (node (ref "U3") (pin "5") (pinfunction "P6.6/A6/DAC0_5") (pintype "passive"))
    )
    (net (code "102") (name "unconnected-(U3-P6.7{slash}A7{slash}DAC1{slash}SVSIN-Pad6)") (class "Default")
      (node (ref "U3") (pin "6") (pinfunction "P6.7/A7/DAC1/SVSIN_6") (pintype "passive"))
    )
    (net (code "103") (name "unconnected-(U3-VREF-{slash}VeREF--Pad11)") (class "Default")
      (node (ref "U3") (pin "11") (pinfunction "VREF-/VeREF-_11") (pintype "passive"))
    )
    (net (code "104") (name "unconnected-(U3-VeREF+-Pad10)") (class "Default")
      (node (ref "U3") (pin "10") (pinfunction "VeREF+_10") (pintype "passive"))
    )
    (net (code "105") (name "unconnected-(U6-+Vo-Pad3)") (class "Default")
      (node (ref "U6") (pin "3") (pinfunction "+Vo_3") (pintype "passive"))
    )
  )
)
